# Microcontroller.net
KiCad netlist of a schematic drawn in Altium Designer
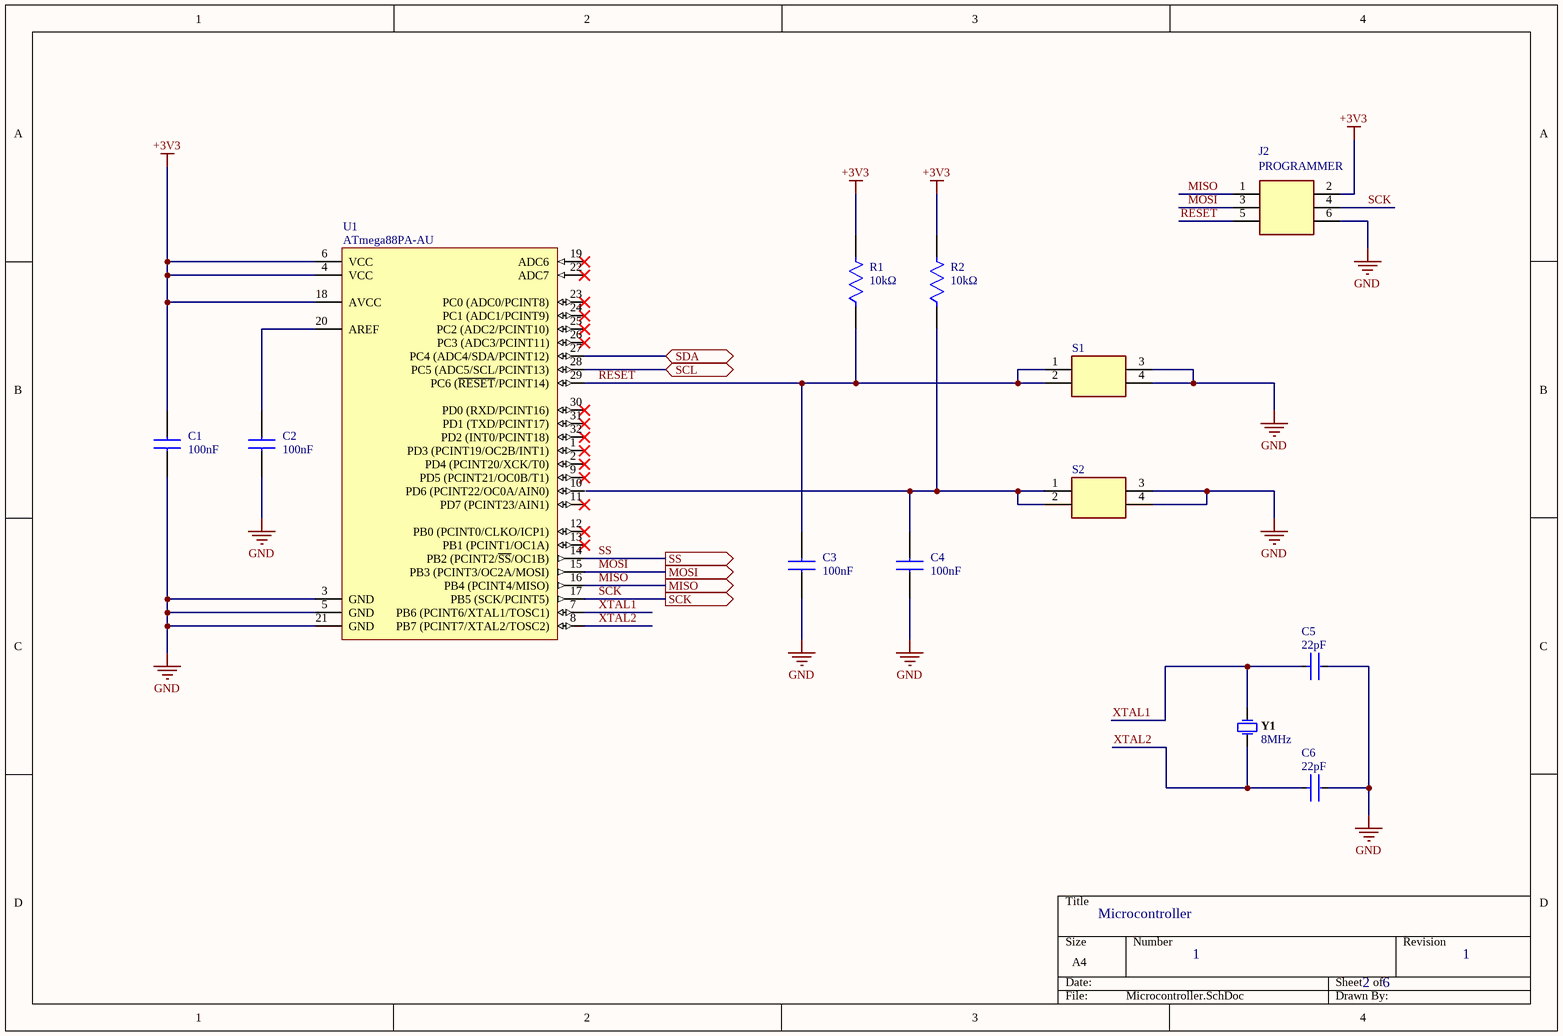
[diagram p0: Microcontroller.SchDoc]

(export (version "E")
  (design (tool "Eeschema 10.0.6"))
  (components
    (comp (ref "C1")
      (value "100nF")
      (footprint "SamacSys:CAPC2013X137N")
      (description "Capacitor")
      (fields
        (field (name "MANUFACTURER_PART_NUMBER") "0805B104K500NT")
        (field (name "MOUSER PART NUMBER") "767-0805B104K500NT")
      )
      (libsource (lib "*") (part "0805B104K500NT"))
    )
    (comp (ref "C2")
      (value "100nF")
      (footprint "SamacSys:CAPC2013X137N")
      (description "Capacitor")
      (fields
        (field (name "MANUFACTURER_PART_NUMBER") "0805B104K500NT")
        (field (name "MOUSER PART NUMBER") "767-0805B104K500NT")
      )
      (libsource (lib "*") (part "0805B104K500NT"))
    )
    (comp (ref "C3")
      (value "100nF")
      (footprint "SamacSys:CAPC2013X137N")
      (description "Capacitor")
      (fields
        (field (name "MANUFACTURER_PART_NUMBER") "0805B104K500NT")
        (field (name "MOUSER PART NUMBER") "767-0805B104K500NT")
      )
      (libsource (lib "*") (part "0805B104K500NT"))
    )
    (comp (ref "C4")
      (value "100nF")
      (footprint "SamacSys:CAPC2013X137N")
      (description "Capacitor")
      (fields
        (field (name "MANUFACTURER_PART_NUMBER") "0805B104K500NT")
        (field (name "MOUSER PART NUMBER") "767-0805B104K500NT")
      )
      (libsource (lib "*") (part "0805B104K500NT"))
    )
    (comp (ref "C5")
      (value "08051A220K4T2A")
      (footprint "FP-0805-L_2_01_0_2-W_1_25-IPC_A")
      (description "Automotive Ceramic Capacitor, 0805, 22pF, 10%, C0G, 30ppm/°C, 100V")
      (fields (field (name "TOLERANCE") "10%") (field (name "CAPACITANCE") "22pF"))
      (libsource (lib "Altium Content Vault") (part "02cd4be3c70576c341d710602a673aa"))
    )
    (comp (ref "C6")
      (value "08051A220K4T2A")
      (footprint "FP-0805-L_2_01_0_2-W_1_25-IPC_A")
      (description "Automotive Ceramic Capacitor, 0805, 22pF, 10%, C0G, 30ppm/°C, 100V")
      (fields (field (name "TOLERANCE") "10%") (field (name "CAPACITANCE") "22pF"))
      (libsource (lib "Altium Content Vault") (part "02cd4be3c70576c341d710602a673aa"))
    )
    (comp (ref "J2")
      (value "90131-0763")
      (footprint "SamacSys:HDRV6W90P254_2X3_762X500X560P")
      (description "Connector")
      (fields (field (name "MOUSER PART NUMBER") "538-90131-0763") (field (name "NAME") "PROGRAMMER"))
      (libsource (lib "*") (part "90131-0763"))
    )
    (comp (ref "R1")
      (value "10kΩ")
      (footprint "FP-CR0805-IPC_A")
      (description "Thick Film Chip Resistors 0805 10kΩ 0.125W 1% 100ppm/°C")
      (fields (field (name "TOLERANCE") "1%") (field (name "Comment") "CR0805-FX-1002ELF"))
      (libsource (lib "Altium Content Vault") (part "1029c3af85768c4190bb7ad29bc67b5"))
    )
    (comp (ref "R2")
      (value "10kΩ")
      (footprint "FP-CR0805-IPC_A")
      (description "Thick Film Chip Resistors 0805 10kΩ 0.125W 1% 100ppm/°C")
      (fields (field (name "TOLERANCE") "1%") (field (name "Comment") "CR0805-FX-1002ELF"))
      (libsource (lib "Altium Content Vault") (part "1029c3af85768c4190bb7ad29bc67b5"))
    )
    (comp (ref "S1")
      (value "1301.9315.24")
      (footprint "SamacSys:13019319")
      (description "Switch")
      (fields (field (name "MOUSER PART NUMBER") "693-1301.9315.24"))
      (libsource (lib "SamacSys") (part "1301.9315.24"))
    )
    (comp (ref "S2")
      (value "1301.9315.24")
      (footprint "SamacSys:13019319")
      (description "Switch")
      (fields (field (name "MOUSER PART NUMBER") "693-1301.9315.24"))
      (libsource (lib "SamacSys") (part "1301.9315.24"))
    )
    (comp (ref "U1")
      (value "ATmega88PA-AU")
      (footprint "32A_L")
      (libsource (lib "Altium Content Vault") (part "MC-8B-ATM48-SQ32"))
    )
    (comp (ref "Y1")
      (value "8MHz")
      (footprint "FOX-FOXSLF080-20")
      (description "Resistance Weld Thru-Hole Crystal, 8 MHz, -20 to 70 degC, 2-Pin THD, RoHS, Bulk")
      (fields (field (name "Comment") "FOXSLF/080-20"))
      (libsource (lib "Altium Content Vault") (part "XTAL-1-2-2"))
    )
  )
  (nets
    (net (code "1") (name "+3V3") (class "Default")
      (node (ref "C1") (pin "1") (pinfunction "1_1") (pintype "passive"))
      (node (ref "J2") (pin "2") (pinfunction "2_2") (pintype "passive"))
      (node (ref "R1") (pin "2") (pinfunction "2_2") (pintype "passive"))
      (node (ref "R2") (pin "2") (pinfunction "2_2") (pintype "passive"))
      (node (ref "U1") (pin "18") (pinfunction "AVCC_18") (pintype "power_in"))
      (node (ref "U1") (pin "4") (pinfunction "VCC_4") (pintype "power_in"))
      (node (ref "U1") (pin "6") (pinfunction "VCC_6") (pintype "power_in"))
    )
    (net (code "2") (name "/MISO") (class "Default")
      (node (ref "J2") (pin "1") (pinfunction "1_1") (pintype "passive"))
      (node (ref "U1") (pin "16") (pinfunction "PB4_(PCINT4/MISO)_16") (pintype "output"))
    )
    (net (code "3") (name "/MOSI") (class "Default")
      (node (ref "J2") (pin "3") (pinfunction "3_3") (pintype "passive"))
      (node (ref "U1") (pin "15") (pinfunction "PB3_(PCINT3/OC2A/MOSI)_15") (pintype "output"))
    )
    (net (code "4") (name "/RESET") (class "Default")
      (node (ref "C3") (pin "1") (pinfunction "1_1") (pintype "passive"))
      (node (ref "J2") (pin "5") (pinfunction "5_5") (pintype "passive"))
      (node (ref "R1") (pin "1") (pinfunction "1_1") (pintype "passive"))
      (node (ref "S1") (pin "1") (pinfunction "NO_1_1") (pintype "passive"))
      (node (ref "S1") (pin "2") (pinfunction "NO_2_2") (pintype "passive"))
      (node (ref "U1") (pin "29") (pinfunction "PC6_(~{RESET}/PCINT14)_29") (pintype "bidirectional"))
    )
    (net (code "5") (name "/SCK") (class "Default")
      (node (ref "J2") (pin "4") (pinfunction "4_4") (pintype "passive"))
      (node (ref "U1") (pin "17") (pinfunction "PB5_(SCK/PCINT5)_17") (pintype "output"))
    )
    (net (code "6") (name "/SCL") (class "Default")
      (node (ref "U1") (pin "28") (pinfunction "PC5_(ADC5/SCL/PCINT13)_28") (pintype "bidirectional"))
    )
    (net (code "7") (name "/SDA") (class "Default")
      (node (ref "U1") (pin "27") (pinfunction "PC4_(ADC4/SDA/PCINT12)_27") (pintype "bidirectional"))
    )
    (net (code "8") (name "/SS") (class "Default")
      (node (ref "U1") (pin "14") (pinfunction "PB2_(PCINT2/~{SS}/OC1B)_14") (pintype "output"))
    )
    (net (code "9") (name "/XTAL1") (class "Default")
      (node (ref "C5") (pin "1") (pinfunction "1_1") (pintype "passive"))
      (node (ref "U1") (pin "7") (pinfunction "PB6_(PCINT6/XTAL1/TOSC1)_7") (pintype "bidirectional"))
      (node (ref "Y1") (pin "2") (pinfunction "2_2") (pintype "passive"))
    )
    (net (code "10") (name "/XTAL2") (class "Default")
      (node (ref "C6") (pin "1") (pinfunction "1_1") (pintype "passive"))
      (node (ref "U1") (pin "8") (pinfunction "PB7_(PCINT7/XTAL2/TOSC2)_8") (pintype "bidirectional"))
      (node (ref "Y1") (pin "1") (pinfunction "1_1") (pintype "passive"))
    )
    (net (code "11") (name "GND") (class "Default")
      (node (ref "C1") (pin "2") (pinfunction "2_2") (pintype "passive"))
      (node (ref "C2") (pin "2") (pinfunction "2_2") (pintype "passive"))
      (node (ref "C3") (pin "2") (pinfunction "2_2") (pintype "passive"))
      (node (ref "C4") (pin "2") (pinfunction "2_2") (pintype "passive"))
      (node (ref "C5") (pin "2") (pinfunction "2_2") (pintype "passive"))
      (node (ref "C6") (pin "2") (pinfunction "2_2") (pintype "passive"))
      (node (ref "J2") (pin "6") (pinfunction "6_6") (pintype "passive"))
      (node (ref "S1") (pin "3") (pinfunction "COM_1_3") (pintype "passive"))
      (node (ref "S1") (pin "4") (pinfunction "COM_2_4") (pintype "passive"))
      (node (ref "S2") (pin "3") (pinfunction "COM_1_3") (pintype "passive"))
      (node (ref "S2") (pin "4") (pinfunction "COM_2_4") (pintype "passive"))
      (node (ref "U1") (pin "21") (pinfunction "GND_21") (pintype "power_in"))
      (node (ref "U1") (pin "3") (pinfunction "GND_3") (pintype "power_in"))
      (node (ref "U1") (pin "5") (pinfunction "GND_5") (pintype "power_in"))
    )
    (net (code "12") (name "Net-(S2-NO_1)") (class "Default")
      (node (ref "C4") (pin "1") (pinfunction "1_1") (pintype "passive"))
      (node (ref "R2") (pin "1") (pinfunction "1_1") (pintype "passive"))
      (node (ref "S2") (pin "1") (pinfunction "NO_1_1") (pintype "passive"))
      (node (ref "S2") (pin "2") (pinfunction "NO_2_2") (pintype "passive"))
    )
    (net (code "13") (name "Net-(U1-AREF)") (class "Default")
      (node (ref "C2") (pin "1") (pinfunction "1_1") (pintype "passive"))
      (node (ref "U1") (pin "20") (pinfunction "AREF_20") (pintype "passive"))
    )
    (net (code "14") (name "unconnected-(U1-ADC6-Pad19)") (class "Default")
      (node (ref "U1") (pin "19") (pinfunction "ADC6_19") (pintype "input+no_connect"))
    )
    (net (code "15") (name "unconnected-(U1-ADC7-Pad22)") (class "Default")
      (node (ref "U1") (pin "22") (pinfunction "ADC7_22") (pintype "input+no_connect"))
    )
    (net (code "16") (name "unconnected-(U1-PB0_(PCINT0{slash}CLKO{slash}ICP1)-Pad12)") (class "Default")
      (node (ref "U1") (pin "12") (pinfunction "PB0_(PCINT0/CLKO/ICP1)_12") (pintype "bidirectional+no_connect"))
    )
    (net (code "17") (name "unconnected-(U1-PB1_(PCINT1{slash}OC1A)-Pad13)") (class "Default")
      (node (ref "U1") (pin "13") (pinfunction "PB1_(PCINT1/OC1A)_13") (pintype "bidirectional+no_connect"))
    )
    (net (code "18") (name "unconnected-(U1-PC0_(ADC0{slash}PCINT8)-Pad23)") (class "Default")
      (node (ref "U1") (pin "23") (pinfunction "PC0_(ADC0/PCINT8)_23") (pintype "bidirectional+no_connect"))
    )
    (net (code "19") (name "unconnected-(U1-PC1_(ADC1{slash}PCINT9)-Pad24)") (class "Default")
      (node (ref "U1") (pin "24") (pinfunction "PC1_(ADC1/PCINT9)_24") (pintype "bidirectional+no_connect"))
    )
    (net (code "20") (name "unconnected-(U1-PC2_(ADC2{slash}PCINT10)-Pad25)") (class "Default")
      (node (ref "U1") (pin "25") (pinfunction "PC2_(ADC2/PCINT10)_25") (pintype "bidirectional+no_connect"))
    )
    (net (code "21") (name "unconnected-(U1-PC3_(ADC3{slash}PCINT11)-Pad26)") (class "Default")
      (node (ref "U1") (pin "26") (pinfunction "PC3_(ADC3/PCINT11)_26") (pintype "bidirectional+no_connect"))
    )
    (net (code "22") (name "unconnected-(U1-PD0_(RXD{slash}PCINT16)-Pad30)") (class "Default")
      (node (ref "U1") (pin "30") (pinfunction "PD0_(RXD/PCINT16)_30") (pintype "bidirectional+no_connect"))
    )
    (net (code "23") (name "unconnected-(U1-PD1_(TXD{slash}PCINT17)-Pad31)") (class "Default")
      (node (ref "U1") (pin "31") (pinfunction "PD1_(TXD/PCINT17)_31") (pintype "bidirectional+no_connect"))
    )
    (net (code "24") (name "unconnected-(U1-PD2_(INT0{slash}PCINT18)-Pad32)") (class "Default")
      (node (ref "U1") (pin "32") (pinfunction "PD2_(INT0/PCINT18)_32") (pintype "bidirectional+no_connect"))
    )
    (net (code "25") (name "unconnected-(U1-PD3_(PCINT19{slash}OC2B{slash}INT1)-Pad1)") (class "Default")
      (node (ref "U1") (pin "1") (pinfunction "PD3_(PCINT19/OC2B/INT1)_1") (pintype "bidirectional+no_connect"))
    )
    (net (code "26") (name "unconnected-(U1-PD4_(PCINT20{slash}XCK{slash}T0)-Pad2)") (class "Default")
      (node (ref "U1") (pin "2") (pinfunction "PD4_(PCINT20/XCK/T0)_2") (pintype "bidirectional+no_connect"))
    )
    (net (code "27") (name "unconnected-(U1-PD5_(PCINT21{slash}OC0B{slash}T1)-Pad9)") (class "Default")
      (node (ref "U1") (pin "9") (pinfunction "PD5_(PCINT21/OC0B/T1)_9") (pintype "bidirectional+no_connect"))
    )
    (net (code "28") (name "unconnected-(U1-PD6_(PCINT22{slash}OC0A{slash}AIN0)-Pad10)") (class "Default")
      (node (ref "U1") (pin "10") (pinfunction "PD6_(PCINT22/OC0A/AIN0)_10") (pintype "bidirectional"))
    )
    (net (code "29") (name "unconnected-(U1-PD7_(PCINT23{slash}AIN1)-Pad11)") (class "Default")
      (node (ref "U1") (pin "11") (pinfunction "PD7_(PCINT23/AIN1)_11") (pintype "bidirectional+no_connect"))
    )
  )
)
